# Blinky_v1.net
KiCad netlist of a schematic drawn in EAGLE
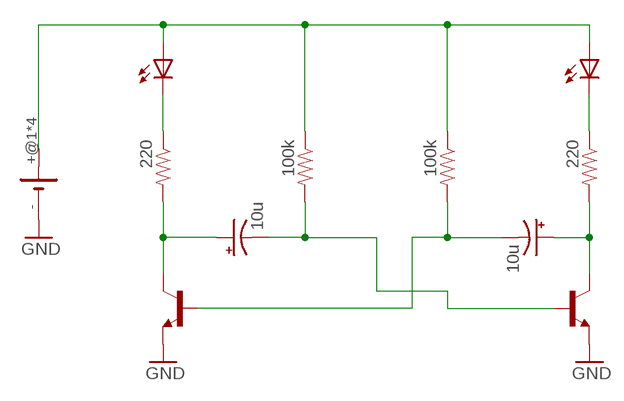
[diagram p0: schematic, sheet 1]

(export (version "E")
  (design (tool "Eeschema 10.0.6"))
  (components
    (comp (ref "BT1")
      (value "BAT-HLD-001-THM")
      (footprint "eagle-import:LINX_BAT-HLD-001-THM")
      (libsource (lib "eagle-import") (part "BAT-HLD-001-THM"))
    )
    (comp (ref "C1")
      (value "10u")
      (footprint "eagle-import:CPOL-RADIAL-10UF-25V")
      (libsource (lib "eagle-import") (part "CAP_POLPTH2"))
    )
    (comp (ref "C2")
      (value "10u")
      (footprint "eagle-import:CPOL-RADIAL-10UF-25V")
      (libsource (lib "eagle-import") (part "CAP_POLPTH2"))
    )
    (comp (ref "LED1")
      (value "RED")
      (footprint "eagle-import:LED5MM")
      (libsource (lib "eagle-import") (part "LED5MM"))
    )
    (comp (ref "LED2")
      (value "RED")
      (footprint "eagle-import:LED5MM")
      (libsource (lib "eagle-import") (part "LED5MM"))
    )
    (comp (ref "R1")
      (value "220")
      (footprint "eagle-import:AXIAL-0.3")
      (libsource (lib "eagle-import") (part "RESISTORAXIAL-0.3"))
    )
    (comp (ref "R2")
      (value "220")
      (footprint "eagle-import:AXIAL-0.3")
      (libsource (lib "eagle-import") (part "RESISTORAXIAL-0.3"))
    )
    (comp (ref "R3")
      (value "100k")
      (footprint "eagle-import:AXIAL-0.3")
      (libsource (lib "eagle-import") (part "RESISTORAXIAL-0.3"))
    )
    (comp (ref "R4")
      (value "100k")
      (footprint "eagle-import:AXIAL-0.3")
      (libsource (lib "eagle-import") (part "RESISTORAXIAL-0.3"))
    )
    (comp (ref "U$1")
      (value "TRANSISTOR_NPN_2PTH")
      (footprint "eagle-import:TO-92")
      (libsource (lib "eagle-import") (part "TRANSISTOR_NPN_2PTH"))
    )
    (comp (ref "U$2")
      (value "TRANSISTOR_NPN_2PTH")
      (footprint "eagle-import:TO-92")
      (libsource (lib "eagle-import") (part "TRANSISTOR_NPN_2PTH"))
    )
  )
  (nets
    (net (code "1") (name "GND") (class "Default")
      (node (ref "BT1") (pin "-") (pinfunction "-_-") (pintype "passive"))
      (node (ref "U$1") (pin "3") (pinfunction "E_3") (pintype "passive"))
      (node (ref "U$2") (pin "3") (pinfunction "E_3") (pintype "passive"))
    )
    (net (code "2") (name "Net-(C1-+)") (class "Default")
      (node (ref "C1") (pin "1") (pinfunction "+_1") (pintype "passive"))
      (node (ref "R1") (pin "P$2") (pinfunction "2_P$2") (pintype "passive"))
      (node (ref "U$1") (pin "1") (pinfunction "C_1") (pintype "passive"))
    )
    (net (code "3") (name "Net-(C1--)") (class "Default")
      (node (ref "C1") (pin "2") (pinfunction "-_2") (pintype "passive"))
      (node (ref "R3") (pin "P$2") (pinfunction "2_P$2") (pintype "passive"))
      (node (ref "U$2") (pin "2") (pinfunction "B_2") (pintype "passive"))
    )
    (net (code "4") (name "Net-(C2-+)") (class "Default")
      (node (ref "C2") (pin "1") (pinfunction "+_1") (pintype "passive"))
      (node (ref "R2") (pin "P$2") (pinfunction "2_P$2") (pintype "passive"))
      (node (ref "U$2") (pin "1") (pinfunction "C_1") (pintype "passive"))
    )
    (net (code "5") (name "Net-(C2--)") (class "Default")
      (node (ref "C2") (pin "2") (pinfunction "-_2") (pintype "passive"))
      (node (ref "R4") (pin "P$2") (pinfunction "2_P$2") (pintype "passive"))
      (node (ref "U$1") (pin "2") (pinfunction "B_2") (pintype "passive"))
    )
    (net (code "6") (name "Net-(LED1-C)") (class "Default")
      (node (ref "LED1") (pin "K") (pinfunction "C_K") (pintype "passive"))
      (node (ref "R1") (pin "P$1") (pinfunction "1_P$1") (pintype "passive"))
    )
    (net (code "7") (name "Net-(LED2-C)") (class "Default")
      (node (ref "LED2") (pin "K") (pinfunction "C_K") (pintype "passive"))
      (node (ref "R2") (pin "P$1") (pinfunction "1_P$1") (pintype "passive"))
    )
    (net (code "8") (name "Net-(R3-1)") (class "Default")
      (node (ref "BT1") (pin "+@1") (pinfunction "+_+@1") (pintype "passive"))
      (node (ref "BT1") (pin "+@2") (pinfunction "+_+@2") (pintype "passive"))
      (node (ref "BT1") (pin "+@3") (pinfunction "+_+@3") (pintype "passive"))
      (node (ref "BT1") (pin "+@4") (pinfunction "+_+@4") (pintype "passive"))
      (node (ref "LED1") (pin "A") (pinfunction "A_A") (pintype "passive"))
      (node (ref "LED2") (pin "A") (pinfunction "A_A") (pintype "passive"))
      (node (ref "R3") (pin "P$1") (pinfunction "1_P$1") (pintype "passive"))
      (node (ref "R4") (pin "P$1") (pinfunction "1_P$1") (pintype "passive"))
    )
  )
)
